# nanov6.net
KiCad netlist of a schematic drawn in EAGLE
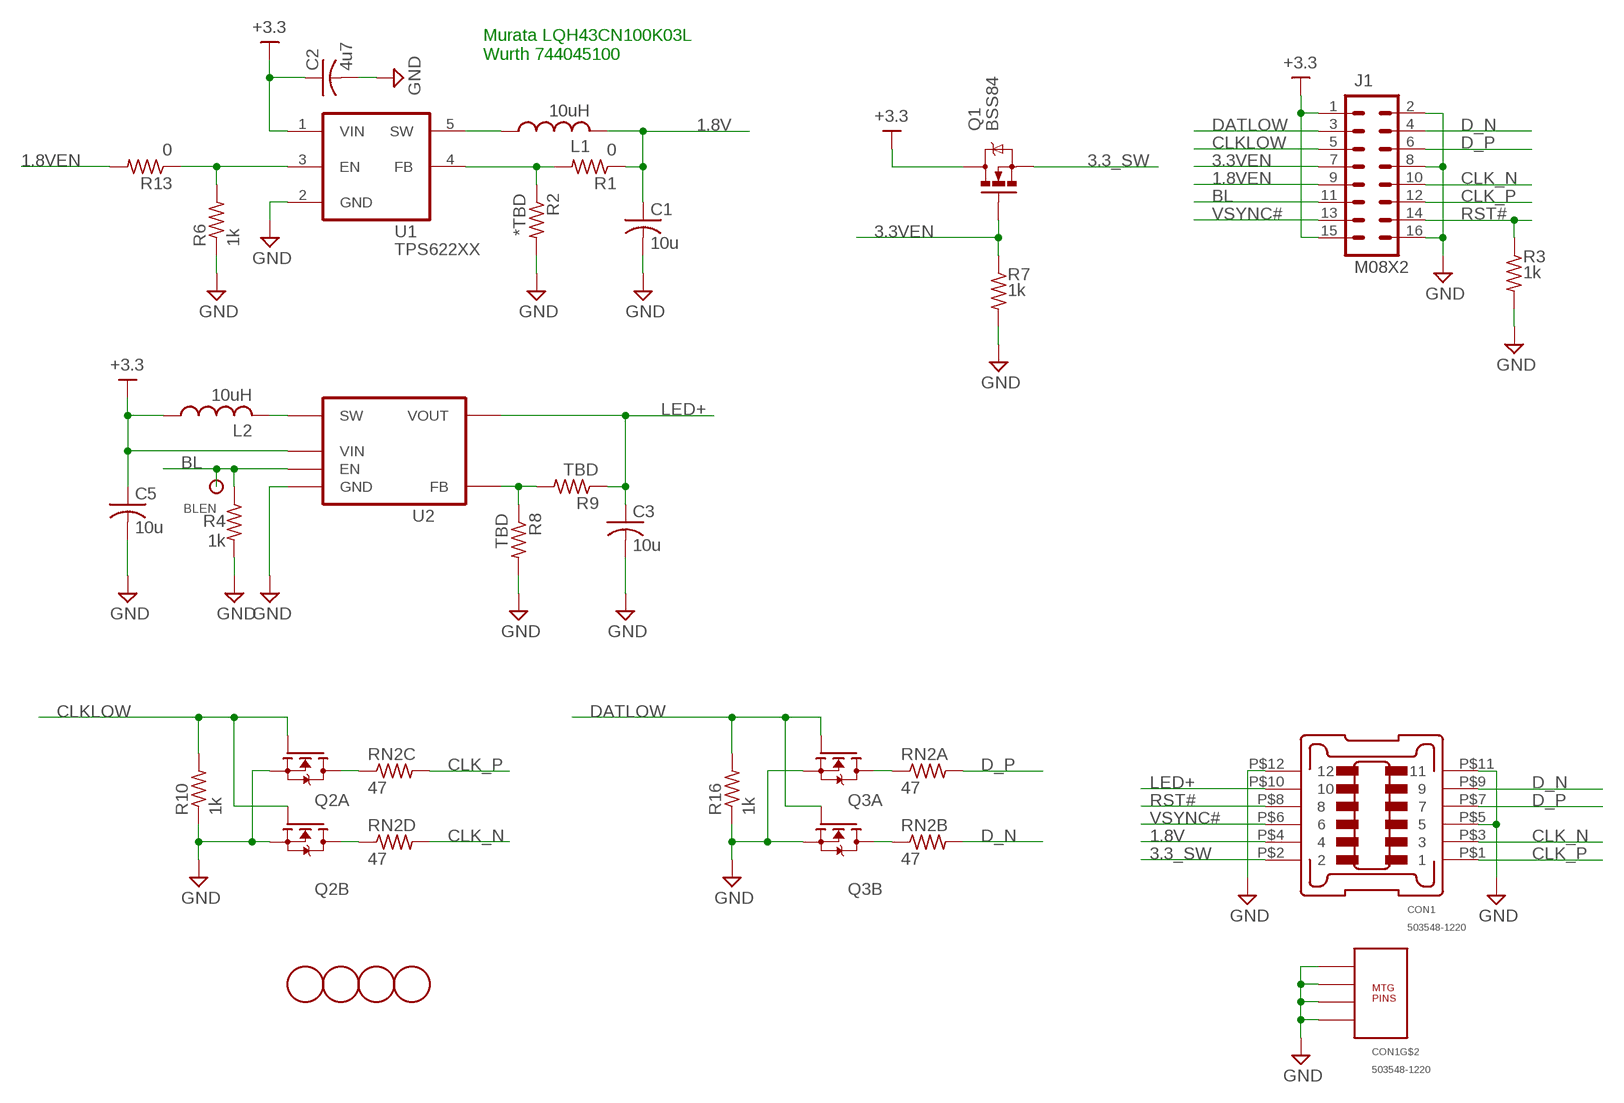
[diagram p0: schematic, sheet 1]

(export (version "E")
  (design (tool "Eeschema 10.0.6"))
  (components
    (comp (ref "BLEN")
      (value "TESTPOINTKEYSTONE_5016")
      (footprint "eagle-import:5016")
      (libsource (lib "eagle-import") (part "TESTPOINTKEYSTONE_5016"))
    )
    (comp (ref "C1")
      (value "10u")
      (footprint "eagle-import:C0805")
      (libsource (lib "eagle-import") (part "C-USC0805"))
    )
    (comp (ref "C2")
      (value "4u7")
      (footprint "eagle-import:C0805")
      (libsource (lib "eagle-import") (part "C-USC0805"))
    )
    (comp (ref "C3")
      (value "10u")
      (footprint "eagle-import:C0805")
      (libsource (lib "eagle-import") (part "C-USC0805"))
    )
    (comp (ref "C5")
      (value "10u")
      (footprint "eagle-import:C0805")
      (libsource (lib "eagle-import") (part "C-USC0805"))
    )
    (comp (ref "CON1")
      (value "503548-1220")
      (footprint "eagle-import:503548-1220")
      (libsource (lib "eagle-import") (part "503548-1220"))
    )
    (comp (ref "J1")
      (value "M08X2")
      (footprint "eagle-import:2X8")
      (libsource (lib "eagle-import") (part "M08X2"))
    )
    (comp (ref "L1")
      (value "10uH")
      (footprint "eagle-import:L1812")
      (libsource (lib "eagle-import") (part "L-USL1812"))
    )
    (comp (ref "L2")
      (value "10uH")
      (footprint "eagle-import:L1812")
      (libsource (lib "eagle-import") (part "L-USL1812"))
    )
    (comp (ref "Q1")
      (value "BSS84")
      (footprint "eagle-import:SOT23-3")
      (libsource (lib "eagle-import") (part "MOSFET-NCHANNELSMD"))
    )
    (comp (ref "Q2")
      (value "2N7002SC70-6")
      (footprint "eagle-import:SC70-6")
      (libsource (lib "eagle-import") (part "2N7002SC70-6"))
    )
    (comp (ref "Q3")
      (value "2N7002SC70-6")
      (footprint "eagle-import:SC70-6")
      (libsource (lib "eagle-import") (part "2N7002SC70-6"))
    )
    (comp (ref "R1")
      (value "0")
      (footprint "eagle-import:R0805")
      (libsource (lib "eagle-import") (part "R-US_R0805"))
    )
    (comp (ref "R2")
      (value "*TBD")
      (footprint "eagle-import:R0805")
      (libsource (lib "eagle-import") (part "R-US_R0805"))
    )
    (comp (ref "R3")
      (value "1k")
      (footprint "eagle-import:R0805")
      (libsource (lib "eagle-import") (part "R-US_R0805"))
    )
    (comp (ref "R4")
      (value "1k")
      (footprint "eagle-import:R0805")
      (libsource (lib "eagle-import") (part "R-US_R0805"))
    )
    (comp (ref "R6")
      (value "1k")
      (footprint "eagle-import:R0805")
      (libsource (lib "eagle-import") (part "R-US_R0805"))
    )
    (comp (ref "R7")
      (value "1k")
      (footprint "eagle-import:R0805")
      (libsource (lib "eagle-import") (part "R-US_R0805"))
    )
    (comp (ref "R8")
      (value "TBD")
      (footprint "eagle-import:R0805")
      (libsource (lib "eagle-import") (part "R-US_R0805"))
    )
    (comp (ref "R9")
      (value "TBD")
      (footprint "eagle-import:R0805")
      (libsource (lib "eagle-import") (part "R-US_R0805"))
    )
    (comp (ref "R10")
      (value "1k")
      (footprint "eagle-import:R0805")
      (libsource (lib "eagle-import") (part "R-US_R0805"))
    )
    (comp (ref "R13")
      (value "0")
      (footprint "eagle-import:R0805")
      (libsource (lib "eagle-import") (part "R-US_R0805"))
    )
    (comp (ref "R16")
      (value "1k")
      (footprint "eagle-import:R0805")
      (libsource (lib "eagle-import") (part "R-US_R0805"))
    )
    (comp (ref "RN2")
      (value "47")
      (footprint "eagle-import:2008")
      (libsource (lib "eagle-import") (part "RES_NETWORK0805"))
    )
    (comp (ref "U$2")
      (value "MOUNTING_HOLE125")
      (footprint "eagle-import:HOLE_MTG_125")
      (libsource (lib "eagle-import") (part "MOUNTING_HOLE125"))
    )
    (comp (ref "U$3")
      (value "MOUNTING_HOLE125")
      (footprint "eagle-import:HOLE_MTG_125")
      (libsource (lib "eagle-import") (part "MOUNTING_HOLE125"))
    )
    (comp (ref "U$11")
      (value "MOUNTING_HOLE125")
      (footprint "eagle-import:HOLE_MTG_125")
      (libsource (lib "eagle-import") (part "MOUNTING_HOLE125"))
    )
    (comp (ref "U$15")
      (value "MOUNTING_HOLE125")
      (footprint "eagle-import:HOLE_MTG_125")
      (libsource (lib "eagle-import") (part "MOUNTING_HOLE125"))
    )
    (comp (ref "U1")
      (value "TPS622XX")
      (footprint "eagle-import:SOT23-5")
      (libsource (lib "eagle-import") (part "TPS622XX"))
    )
    (comp (ref "U2")
      (value "TLV61220")
      (footprint "eagle-import:SOT23-6")
      (libsource (lib "eagle-import") (part "TLV61220"))
    )
  )
  (nets
    (net (code "1") (name "+3.3") (class "Default")
      (node (ref "C2") (pin "1") (pinfunction "1_1") (pintype "passive"))
      (node (ref "C5") (pin "1") (pinfunction "1_1") (pintype "passive"))
      (node (ref "J1") (pin "1") (pinfunction "1_1") (pintype "passive"))
      (node (ref "J1") (pin "15") (pinfunction "15_15") (pintype "passive"))
      (node (ref "L2") (pin "1") (pinfunction "1_1") (pintype "passive"))
      (node (ref "Q1") (pin "3") (pinfunction "D_3") (pintype "passive"))
      (node (ref "U1") (pin "1") (pinfunction "VIN_1") (pintype "passive"))
      (node (ref "U2") (pin "6") (pinfunction "VIN_6") (pintype "passive"))
    )
    (net (code "2") (name "/1.8V") (class "Default")
      (node (ref "C1") (pin "1") (pinfunction "1_1") (pintype "passive"))
      (node (ref "CON1") (pin "P$4") (pinfunction "4_P$4") (pintype "passive"))
      (node (ref "L1") (pin "2") (pinfunction "2_2") (pintype "passive"))
      (node (ref "R1") (pin "1") (pinfunction "1_1") (pintype "passive"))
    )
    (net (code "3") (name "/1.8VEN") (class "Default")
      (node (ref "J1") (pin "9") (pinfunction "9_9") (pintype "passive"))
      (node (ref "R13") (pin "2") (pinfunction "2_2") (pintype "passive"))
    )
    (net (code "4") (name "/3.3VEN") (class "Default")
      (node (ref "J1") (pin "7") (pinfunction "7_7") (pintype "passive"))
      (node (ref "Q1") (pin "1") (pinfunction "G_1") (pintype "passive"))
      (node (ref "R7") (pin "1") (pinfunction "1_1") (pintype "passive"))
    )
    (net (code "5") (name "/3.3_SW") (class "Default")
      (node (ref "CON1") (pin "P$2") (pinfunction "2_P$2") (pintype "passive"))
      (node (ref "Q1") (pin "2") (pinfunction "S_2") (pintype "passive"))
    )
    (net (code "6") (name "/BL") (class "Default")
      (node (ref "BLEN") (pin "P$1") (pinfunction "1_P$1") (pintype "passive"))
      (node (ref "J1") (pin "11") (pinfunction "11_11") (pintype "passive"))
      (node (ref "R4") (pin "1") (pinfunction "1_1") (pintype "passive"))
      (node (ref "U2") (pin "3") (pinfunction "EN_3") (pintype "input"))
    )
    (net (code "7") (name "/CLKLOW") (class "Default")
      (node (ref "J1") (pin "5") (pinfunction "5_5") (pintype "passive"))
      (node (ref "Q2") (pin "2") (pinfunction "G_2") (pintype "passive"))
      (node (ref "Q2") (pin "5") (pinfunction "G_5") (pintype "passive"))
      (node (ref "R10") (pin "2") (pinfunction "2_2") (pintype "passive"))
    )
    (net (code "8") (name "/CLK_N") (class "Default")
      (node (ref "CON1") (pin "P$3") (pinfunction "3_P$3") (pintype "passive"))
      (node (ref "J1") (pin "10") (pinfunction "10_10") (pintype "passive"))
      (node (ref "RN2") (pin "5") (pinfunction "2_5") (pintype "passive"))
    )
    (net (code "9") (name "/CLK_P") (class "Default")
      (node (ref "CON1") (pin "P$1") (pinfunction "1_P$1") (pintype "passive"))
      (node (ref "J1") (pin "12") (pinfunction "12_12") (pintype "passive"))
      (node (ref "RN2") (pin "6") (pinfunction "2_6") (pintype "passive"))
    )
    (net (code "10") (name "/DATLOW") (class "Default")
      (node (ref "J1") (pin "3") (pinfunction "3_3") (pintype "passive"))
      (node (ref "Q3") (pin "2") (pinfunction "G_2") (pintype "passive"))
      (node (ref "Q3") (pin "5") (pinfunction "G_5") (pintype "passive"))
      (node (ref "R16") (pin "2") (pinfunction "2_2") (pintype "passive"))
    )
    (net (code "11") (name "/D_N") (class "Default")
      (node (ref "CON1") (pin "P$9") (pinfunction "9_P$9") (pintype "passive"))
      (node (ref "J1") (pin "4") (pinfunction "4_4") (pintype "passive"))
      (node (ref "RN2") (pin "7") (pinfunction "2_7") (pintype "passive"))
    )
    (net (code "12") (name "/D_P") (class "Default")
      (node (ref "CON1") (pin "P$7") (pinfunction "7_P$7") (pintype "passive"))
      (node (ref "J1") (pin "6") (pinfunction "6_6") (pintype "passive"))
      (node (ref "RN2") (pin "8") (pinfunction "2_8") (pintype "passive"))
    )
    (net (code "13") (name "/LED+") (class "Default")
      (node (ref "C3") (pin "1") (pinfunction "1_1") (pintype "passive"))
      (node (ref "CON1") (pin "P$10") (pinfunction "10_P$10") (pintype "passive"))
      (node (ref "R9") (pin "1") (pinfunction "1_1") (pintype "passive"))
      (node (ref "U2") (pin "5") (pinfunction "VOUT_5") (pintype "passive"))
    )
    (net (code "14") (name "/RST#") (class "Default")
      (node (ref "CON1") (pin "P$8") (pinfunction "8_P$8") (pintype "passive"))
      (node (ref "J1") (pin "14") (pinfunction "14_14") (pintype "passive"))
      (node (ref "R3") (pin "1") (pinfunction "1_1") (pintype "passive"))
    )
    (net (code "15") (name "/VSYNC#") (class "Default")
      (node (ref "CON1") (pin "P$6") (pinfunction "6_P$6") (pintype "passive"))
      (node (ref "J1") (pin "13") (pinfunction "13_13") (pintype "passive"))
    )
    (net (code "16") (name "GND") (class "Default")
      (node (ref "C1") (pin "2") (pinfunction "2_2") (pintype "passive"))
      (node (ref "C2") (pin "2") (pinfunction "2_2") (pintype "passive"))
      (node (ref "C3") (pin "2") (pinfunction "2_2") (pintype "passive"))
      (node (ref "C5") (pin "2") (pinfunction "2_2") (pintype "passive"))
      (node (ref "CON1") (pin "MTG1") (pinfunction "P$1_MTG1") (pintype "passive"))
      (node (ref "CON1") (pin "MTG2") (pinfunction "P$2_MTG2") (pintype "passive"))
      (node (ref "CON1") (pin "MTG3") (pinfunction "P$3_MTG3") (pintype "passive"))
      (node (ref "CON1") (pin "MTG4") (pinfunction "P$4_MTG4") (pintype "passive"))
      (node (ref "CON1") (pin "P$11") (pinfunction "11_P$11") (pintype "passive"))
      (node (ref "CON1") (pin "P$12") (pinfunction "12_P$12") (pintype "passive"))
      (node (ref "CON1") (pin "P$5") (pinfunction "5_P$5") (pintype "passive"))
      (node (ref "J1") (pin "16") (pinfunction "16_16") (pintype "passive"))
      (node (ref "J1") (pin "2") (pinfunction "2_2") (pintype "passive"))
      (node (ref "J1") (pin "8") (pinfunction "8_8") (pintype "passive"))
      (node (ref "Q2") (pin "1") (pinfunction "S_1") (pintype "passive"))
      (node (ref "Q2") (pin "4") (pinfunction "S_4") (pintype "passive"))
      (node (ref "Q3") (pin "1") (pinfunction "S_1") (pintype "passive"))
      (node (ref "Q3") (pin "4") (pinfunction "S_4") (pintype "passive"))
      (node (ref "R10") (pin "1") (pinfunction "1_1") (pintype "passive"))
      (node (ref "R16") (pin "1") (pinfunction "1_1") (pintype "passive"))
      (node (ref "R2") (pin "2") (pinfunction "2_2") (pintype "passive"))
      (node (ref "R3") (pin "2") (pinfunction "2_2") (pintype "passive"))
      (node (ref "R4") (pin "2") (pinfunction "2_2") (pintype "passive"))
      (node (ref "R6") (pin "1") (pinfunction "1_1") (pintype "passive"))
      (node (ref "R7") (pin "2") (pinfunction "2_2") (pintype "passive"))
      (node (ref "R8") (pin "2") (pinfunction "2_2") (pintype "passive"))
      (node (ref "U1") (pin "2") (pinfunction "GND_2") (pintype "power_in"))
      (node (ref "U2") (pin "2") (pinfunction "GND_2") (pintype "power_in"))
    )
    (net (code "17") (name "Net-(Q2A-D)") (class "Default")
      (node (ref "Q2") (pin "3") (pinfunction "D_3") (pintype "passive"))
      (node (ref "RN2") (pin "3") (pinfunction "1_3") (pintype "passive"))
    )
    (net (code "18") (name "Net-(Q2B-D)") (class "Default")
      (node (ref "Q2") (pin "6") (pinfunction "D_6") (pintype "passive"))
      (node (ref "RN2") (pin "4") (pinfunction "1_4") (pintype "passive"))
    )
    (net (code "19") (name "Net-(Q3A-D)") (class "Default")
      (node (ref "Q3") (pin "3") (pinfunction "D_3") (pintype "passive"))
      (node (ref "RN2") (pin "1") (pinfunction "1_1") (pintype "passive"))
    )
    (net (code "20") (name "Net-(Q3B-D)") (class "Default")
      (node (ref "Q3") (pin "6") (pinfunction "D_6") (pintype "passive"))
      (node (ref "RN2") (pin "2") (pinfunction "1_2") (pintype "passive"))
    )
    (net (code "21") (name "Net-(U1-EN)") (class "Default")
      (node (ref "R13") (pin "1") (pinfunction "1_1") (pintype "passive"))
      (node (ref "R6") (pin "2") (pinfunction "2_2") (pintype "passive"))
      (node (ref "U1") (pin "3") (pinfunction "EN_3") (pintype "input"))
    )
    (net (code "22") (name "Net-(U1-FB)") (class "Default")
      (node (ref "R1") (pin "2") (pinfunction "2_2") (pintype "passive"))
      (node (ref "R2") (pin "1") (pinfunction "1_1") (pintype "passive"))
      (node (ref "U1") (pin "4") (pinfunction "FB_4") (pintype "passive"))
    )
    (net (code "23") (name "Net-(U1-SW)") (class "Default")
      (node (ref "L1") (pin "1") (pinfunction "1_1") (pintype "passive"))
      (node (ref "U1") (pin "5") (pinfunction "SW_5") (pintype "passive"))
    )
    (net (code "24") (name "Net-(U2-FB)") (class "Default")
      (node (ref "R8") (pin "1") (pinfunction "1_1") (pintype "passive"))
      (node (ref "R9") (pin "2") (pinfunction "2_2") (pintype "passive"))
      (node (ref "U2") (pin "4") (pinfunction "FB_4") (pintype "passive"))
    )
    (net (code "25") (name "Net-(U2-SW)") (class "Default")
      (node (ref "L2") (pin "2") (pinfunction "2_2") (pintype "passive"))
      (node (ref "U2") (pin "1") (pinfunction "SW_1") (pintype "passive"))
    )
  )
)
